# BacKey_for_MaKey_MaKey_rev_A.net
KiCad netlist of a schematic drawn in EAGLE
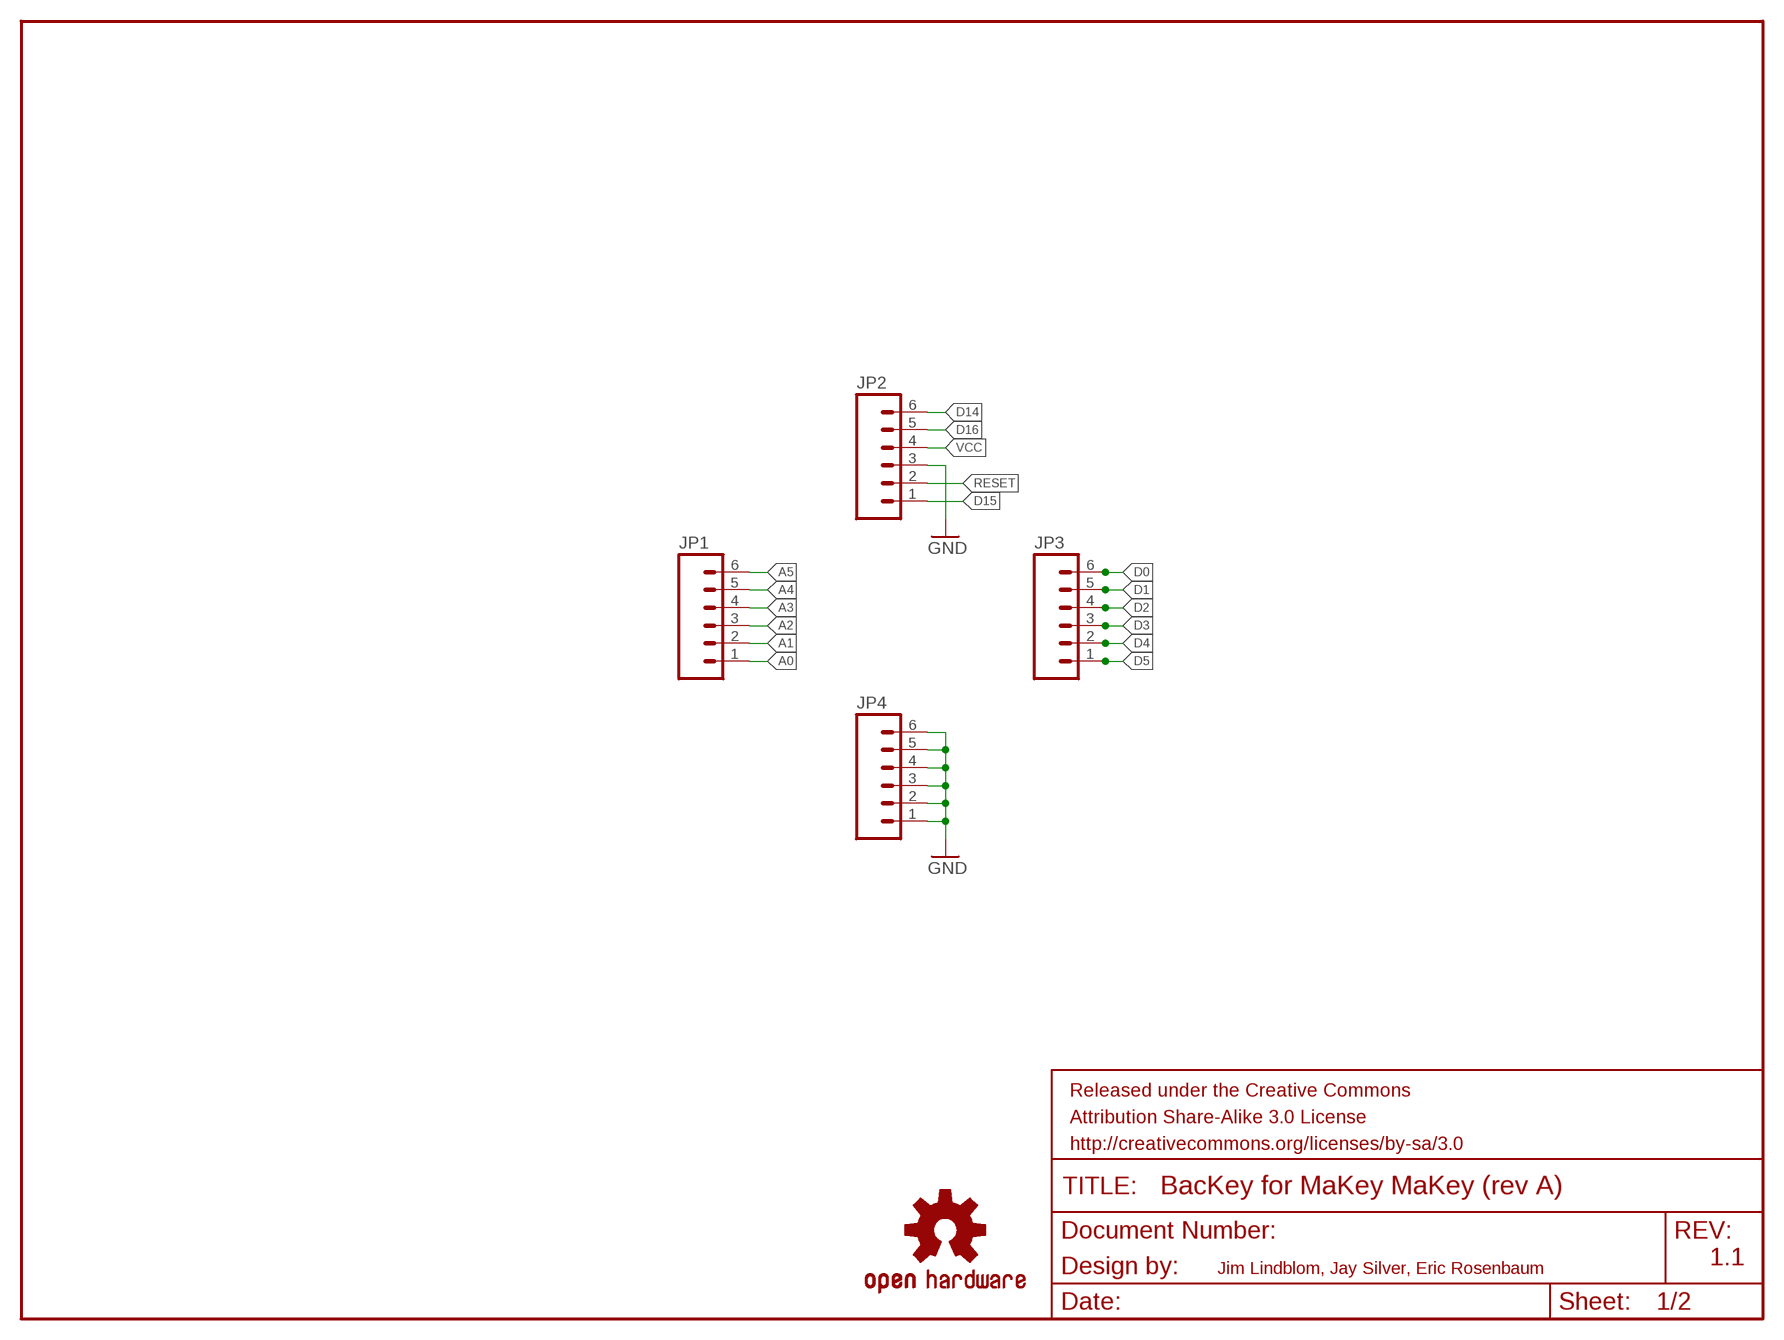
[diagram p0: schematic, sheet 1]
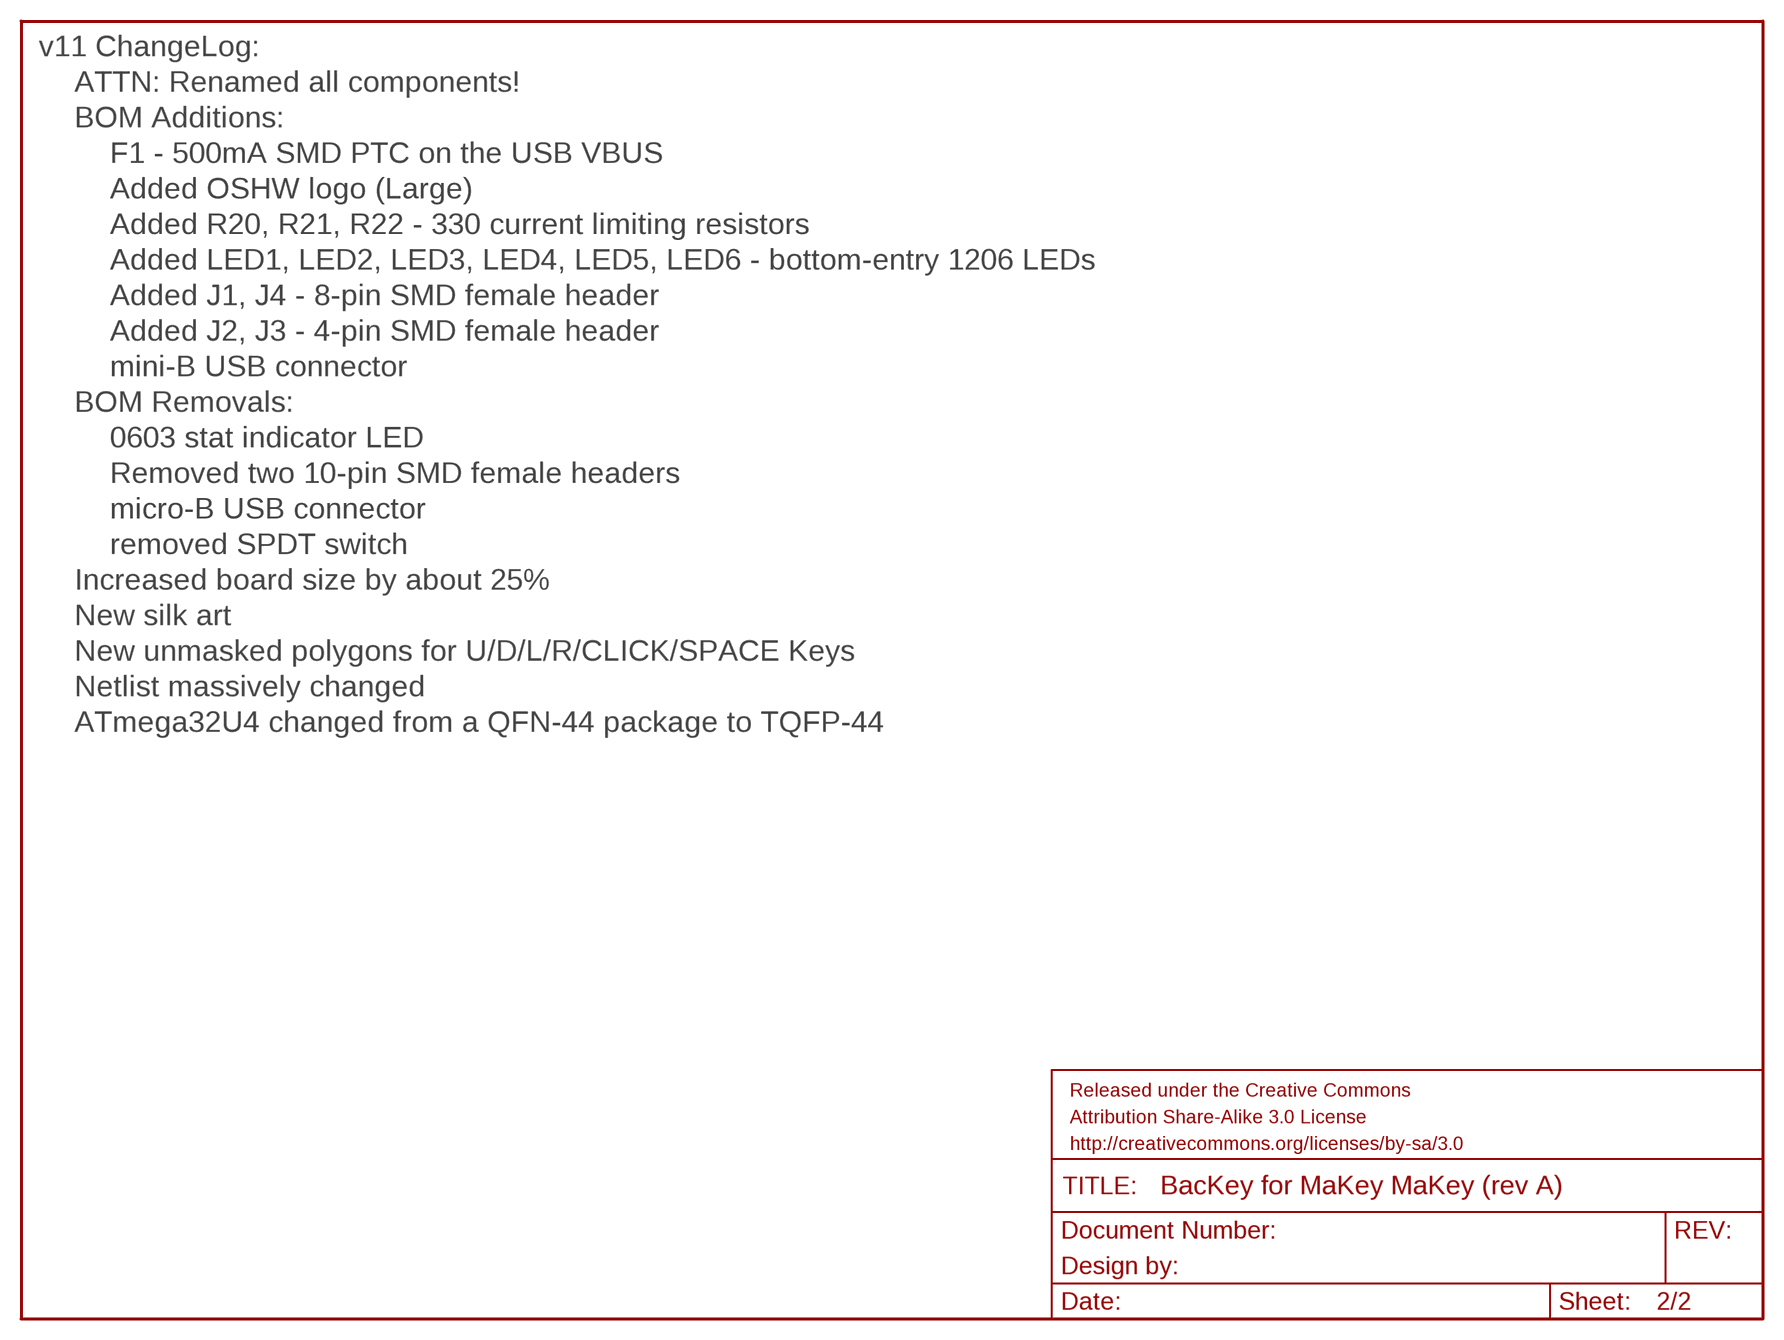
[diagram p1: schematic, sheet 2]

(export (version "E")
  (design (tool "Eeschema 10.0.6"))
  (components
    (comp (ref "JP1")
      (value "M06SIP")
      (footprint "eagle-import:1X06")
      (libsource (lib "eagle-import") (part "M06SIP"))
    )
    (comp (ref "JP2")
      (value "M06SIP")
      (footprint "eagle-import:1X06")
      (libsource (lib "eagle-import") (part "M06SIP"))
    )
    (comp (ref "JP3")
      (value "M06SIP")
      (footprint "eagle-import:1X06")
      (libsource (lib "eagle-import") (part "M06SIP"))
    )
    (comp (ref "JP4")
      (value "M06SIP")
      (footprint "eagle-import:1X06")
      (libsource (lib "eagle-import") (part "M06SIP"))
    )
    (comp (ref "U$1")
      (value "OSHW-LOGOM")
      (footprint "eagle-import:OSHW-LOGO-M")
      (libsource (lib "eagle-import") (part "OSHW-LOGOM"))
    )
  )
  (nets
    (net (code "1") (name "A0") (class "Default")
      (node (ref "JP1") (pin "1") (pinfunction "1_1") (pintype "passive"))
    )
    (net (code "2") (name "A1") (class "Default")
      (node (ref "JP1") (pin "2") (pinfunction "2_2") (pintype "passive"))
    )
    (net (code "3") (name "A2") (class "Default")
      (node (ref "JP1") (pin "3") (pinfunction "3_3") (pintype "passive"))
    )
    (net (code "4") (name "A3") (class "Default")
      (node (ref "JP1") (pin "4") (pinfunction "4_4") (pintype "passive"))
    )
    (net (code "5") (name "A4") (class "Default")
      (node (ref "JP1") (pin "5") (pinfunction "5_5") (pintype "passive"))
    )
    (net (code "6") (name "A5") (class "Default")
      (node (ref "JP1") (pin "6") (pinfunction "6_6") (pintype "passive"))
    )
    (net (code "7") (name "D0") (class "Default")
      (node (ref "JP3") (pin "6") (pinfunction "6_6") (pintype "passive"))
    )
    (net (code "8") (name "D1") (class "Default")
      (node (ref "JP3") (pin "5") (pinfunction "5_5") (pintype "passive"))
    )
    (net (code "9") (name "D2") (class "Default")
      (node (ref "JP3") (pin "4") (pinfunction "4_4") (pintype "passive"))
    )
    (net (code "10") (name "D3") (class "Default")
      (node (ref "JP3") (pin "3") (pinfunction "3_3") (pintype "passive"))
    )
    (net (code "11") (name "D4") (class "Default")
      (node (ref "JP3") (pin "2") (pinfunction "2_2") (pintype "passive"))
    )
    (net (code "12") (name "D5") (class "Default")
      (node (ref "JP3") (pin "1") (pinfunction "1_1") (pintype "passive"))
    )
    (net (code "13") (name "D14") (class "Default")
      (node (ref "JP2") (pin "6") (pinfunction "6_6") (pintype "passive"))
    )
    (net (code "14") (name "D15") (class "Default")
      (node (ref "JP2") (pin "1") (pinfunction "1_1") (pintype "passive"))
    )
    (net (code "15") (name "D16") (class "Default")
      (node (ref "JP2") (pin "5") (pinfunction "5_5") (pintype "passive"))
    )
    (net (code "16") (name "GND") (class "Default")
      (node (ref "JP2") (pin "3") (pinfunction "3_3") (pintype "passive"))
      (node (ref "JP4") (pin "1") (pinfunction "1_1") (pintype "passive"))
      (node (ref "JP4") (pin "2") (pinfunction "2_2") (pintype "passive"))
      (node (ref "JP4") (pin "3") (pinfunction "3_3") (pintype "passive"))
      (node (ref "JP4") (pin "4") (pinfunction "4_4") (pintype "passive"))
      (node (ref "JP4") (pin "5") (pinfunction "5_5") (pintype "passive"))
      (node (ref "JP4") (pin "6") (pinfunction "6_6") (pintype "passive"))
    )
    (net (code "17") (name "RESET") (class "Default")
      (node (ref "JP2") (pin "2") (pinfunction "2_2") (pintype "passive"))
    )
    (net (code "18") (name "VCC") (class "Default")
      (node (ref "JP2") (pin "4") (pinfunction "4_4") (pintype "passive"))
    )
  )
)
